# Sheet1.net
KiCad netlist of a schematic drawn in Altium Designer
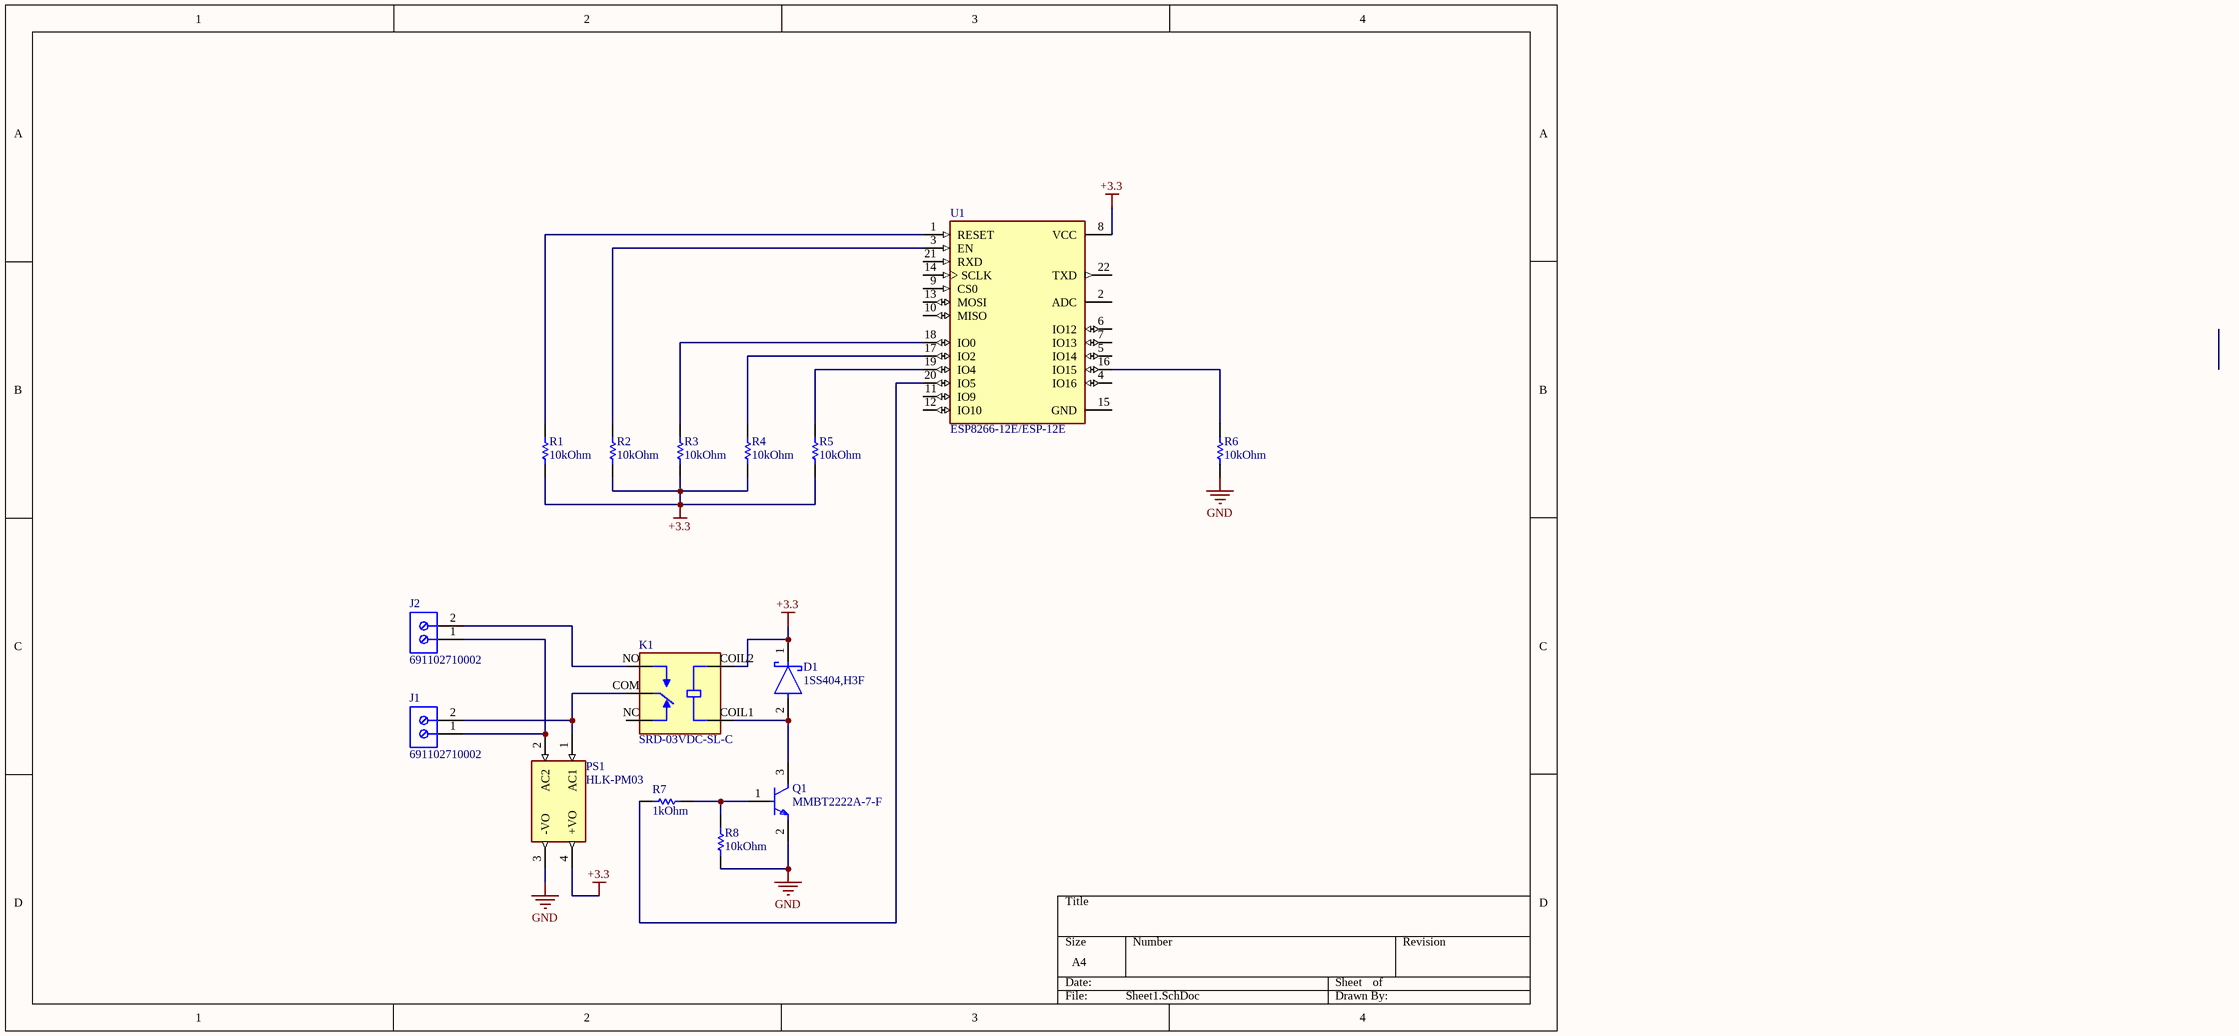
[diagram p0: Sheet1.SchDoc]

(export (version "E")
  (design (tool "Eeschema 10.0.6"))
  (components
    (comp (ref "D1")
      (value "1SS404,H3F")
      (footprint "FP-SOD-323-MFG")
      (description "DIODE SCHOTTKY 20V 300MA USC")
      (libsource (lib "Altium Content Vault") (part "1d6ec82d83fb6aee721767c19dac4b9"))
    )
    (comp (ref "J1")
      (value "691102710002")
      (footprint "691102710002")
      (fields (field (name "VOLTAGE") "300V"))
      (libsource (lib "Altium Content Vault") (part "TBL - 1R - 02P - Screw"))
    )
    (comp (ref "J2")
      (value "691102710002")
      (footprint "691102710002")
      (fields (field (name "VOLTAGE") "300V"))
      (libsource (lib "Altium Content Vault") (part "TBL - 1R - 02P - Screw"))
    )
    (comp (ref "K1")
      (value "SRD-03VDC-SL-C")
      (footprint "SRD-03VDC-SL-C:RELAY_SRD-03VDC-SL-C")
      (fields (field (name "MF") "{'manufacturer': u'Songle Relay'}"))
      (libsource (lib "*") (part "SRD-03VDC-SL-C"))
    )
    (comp (ref "PS1")
      (value "HLK-PM03")
      (footprint "HLK-PM03:CONV_HLK-PM03")
      (fields (field (name "MF") "{'manufacturer': u'Hi-link'}"))
      (libsource (lib "*") (part "HLK-PM03"))
    )
    (comp (ref "Q1")
      (value "MMBT2222A-7-F")
      (footprint "FP-SOT23-IPC_A")
      (description "TRANS NPN 40V 0.6A SMD SOT23-3")
      (fields (field (name "VOLTAGE") "40V"))
      (libsource (lib "Altium Content Vault") (part "b44e953556f554d0102664c7d152cb4"))
    )
    (comp (ref "R1")
      (value "10kOhm")
      (footprint "RESC1609X50X30ML10T20")
      (fields (field (name "MANUFACTURER") "Vishay Dale") (field (name "PART NUMBER") "CRCW060310K0FKTB"))
      (libsource (lib "Altium Content Vault") (part "RES"))
    )
    (comp (ref "R2")
      (value "10kOhm")
      (footprint "RESC1609X50X30ML10T20")
      (fields (field (name "MANUFACTURER") "Vishay Dale") (field (name "PART NUMBER") "CRCW060310K0FKTB"))
      (libsource (lib "Altium Content Vault") (part "RES"))
    )
    (comp (ref "R3")
      (value "10kOhm")
      (footprint "RESC1609X50X30ML10T20")
      (fields (field (name "MANUFACTURER") "Vishay Dale") (field (name "PART NUMBER") "CRCW060310K0FKTB"))
      (libsource (lib "Altium Content Vault") (part "RES"))
    )
    (comp (ref "R4")
      (value "10kOhm")
      (footprint "RESC1609X50X30ML10T20")
      (fields (field (name "MANUFACTURER") "Vishay Dale") (field (name "PART NUMBER") "CRCW060310K0FKTB"))
      (libsource (lib "Altium Content Vault") (part "RES"))
    )
    (comp (ref "R5")
      (value "10kOhm")
      (footprint "RESC1609X50X30ML10T20")
      (fields (field (name "MANUFACTURER") "Vishay Dale") (field (name "PART NUMBER") "CRCW060310K0FKTB"))
      (libsource (lib "Altium Content Vault") (part "RES"))
    )
    (comp (ref "R6")
      (value "10kOhm")
      (footprint "RESC1609X50X30ML10T20")
      (fields (field (name "MANUFACTURER") "Vishay Dale") (field (name "PART NUMBER") "CRCW060310K0FKTB"))
      (libsource (lib "Altium Content Vault") (part "RES"))
    )
    (comp (ref "R7")
      (value "1kOhm")
      (footprint "RESC1609X50X30ML10T20")
      (fields (field (name "MANUFACTURER") "Vishay Dale") (field (name "PART NUMBER") "CRCW060310K0FKTB"))
      (libsource (lib "Altium Content Vault") (part "RES"))
    )
    (comp (ref "R8")
      (value "10kOhm")
      (footprint "RESC1609X50X30ML10T20")
      (fields (field (name "MANUFACTURER") "Vishay Dale") (field (name "PART NUMBER") "CRCW060310K0FKTB"))
      (libsource (lib "Altium Content Vault") (part "RES"))
    )
    (comp (ref "U1")
      (value "ESP8266-12E/ESP-12E")
      (footprint "ESP8266-12E_ESP-12E:XCVR_ESP8266-12E/ESP-12E")
      (description "ESP-12E WiFi Module")
      (fields (field (name "MF") "{'manufacturer': u'AI-Thinker'}"))
      (libsource (lib "*") (part "ESP8266-12E/ESP-12E"))
    )
  )
  (nets
    (net (code "1") (name "+3.3") (class "Default")
      (node (ref "D1") (pin "1") (pinfunction "C_1") (pintype "passive"))
      (node (ref "K1") (pin "COIL2") (pinfunction "COIL2_COIL2") (pintype "passive"))
      (node (ref "PS1") (pin "4") (pinfunction "+VO_4") (pintype "output"))
      (node (ref "R1") (pin "1") (pinfunction "1_1") (pintype "passive"))
      (node (ref "R2") (pin "1") (pinfunction "1_1") (pintype "passive"))
      (node (ref "R3") (pin "1") (pinfunction "1_1") (pintype "passive"))
      (node (ref "R4") (pin "1") (pinfunction "1_1") (pintype "passive"))
      (node (ref "R5") (pin "1") (pinfunction "1_1") (pintype "passive"))
      (node (ref "U1") (pin "8") (pinfunction "VCC_8") (pintype "power_in"))
    )
    (net (code "2") (name "GND") (class "Default")
      (node (ref "PS1") (pin "3") (pinfunction "-VO_3") (pintype "output"))
      (node (ref "Q1") (pin "2") (pinfunction "E_2") (pintype "passive"))
      (node (ref "R6") (pin "1") (pinfunction "1_1") (pintype "passive"))
      (node (ref "R8") (pin "1") (pinfunction "1_1") (pintype "passive"))
    )
    (net (code "3") (name "Net-(D1-A)") (class "Default")
      (node (ref "D1") (pin "2") (pinfunction "A_2") (pintype "passive"))
      (node (ref "K1") (pin "COIL1") (pinfunction "COIL1_COIL1") (pintype "passive"))
      (node (ref "Q1") (pin "3") (pinfunction "C_3") (pintype "passive"))
    )
    (net (code "4") (name "Net-(J2-Pad2)") (class "Default")
      (node (ref "J2") (pin "2") (pinfunction "2_2") (pintype "passive"))
      (node (ref "K1") (pin "NO") (pinfunction "NO_NO") (pintype "passive"))
    )
    (net (code "5") (name "Net-(PS1-AC1)") (class "Default")
      (node (ref "J1") (pin "2") (pinfunction "2_2") (pintype "passive"))
      (node (ref "K1") (pin "COM") (pinfunction "COM_COM") (pintype "passive"))
      (node (ref "PS1") (pin "1") (pinfunction "AC1_1") (pintype "input"))
    )
    (net (code "6") (name "Net-(PS1-AC2)") (class "Default")
      (node (ref "J1") (pin "1") (pinfunction "1_1") (pintype "passive"))
      (node (ref "J2") (pin "1") (pinfunction "1_1") (pintype "passive"))
      (node (ref "PS1") (pin "2") (pinfunction "AC2_2") (pintype "input"))
    )
    (net (code "7") (name "Net-(Q1-B)") (class "Default")
      (node (ref "Q1") (pin "1") (pinfunction "B_1") (pintype "passive"))
      (node (ref "R7") (pin "2") (pinfunction "2_2") (pintype "passive"))
      (node (ref "R8") (pin "2") (pinfunction "2_2") (pintype "passive"))
    )
    (net (code "8") (name "Net-(U1-EN)") (class "Default")
      (node (ref "R2") (pin "2") (pinfunction "2_2") (pintype "passive"))
      (node (ref "U1") (pin "3") (pinfunction "EN_3") (pintype "input"))
    )
    (net (code "9") (name "Net-(U1-IO0)") (class "Default")
      (node (ref "R3") (pin "2") (pinfunction "2_2") (pintype "passive"))
      (node (ref "U1") (pin "18") (pinfunction "IO0_18") (pintype "bidirectional"))
    )
    (net (code "10") (name "Net-(U1-IO2)") (class "Default")
      (node (ref "R4") (pin "2") (pinfunction "2_2") (pintype "passive"))
      (node (ref "U1") (pin "17") (pinfunction "IO2_17") (pintype "bidirectional"))
    )
    (net (code "11") (name "Net-(U1-IO4)") (class "Default")
      (node (ref "R5") (pin "2") (pinfunction "2_2") (pintype "passive"))
      (node (ref "U1") (pin "19") (pinfunction "IO4_19") (pintype "bidirectional"))
    )
    (net (code "12") (name "Net-(U1-IO5)") (class "Default")
      (node (ref "R7") (pin "1") (pinfunction "1_1") (pintype "passive"))
      (node (ref "U1") (pin "20") (pinfunction "IO5_20") (pintype "bidirectional"))
    )
    (net (code "13") (name "Net-(U1-IO15)") (class "Default")
      (node (ref "R6") (pin "2") (pinfunction "2_2") (pintype "passive"))
      (node (ref "U1") (pin "16") (pinfunction "IO15_16") (pintype "bidirectional"))
    )
    (net (code "14") (name "Net-(U1-RESET)") (class "Default")
      (node (ref "R1") (pin "2") (pinfunction "2_2") (pintype "passive"))
      (node (ref "U1") (pin "1") (pinfunction "RESET_1") (pintype "input"))
    )
    (net (code "15") (name "unconnected-(K1-PadNC)") (class "Default")
      (node (ref "K1") (pin "NC") (pinfunction "NC_NC") (pintype "passive"))
    )
    (net (code "16") (name "unconnected-(U1-ADC-Pad2)") (class "Default")
      (node (ref "U1") (pin "2") (pinfunction "ADC_2") (pintype "passive"))
    )
    (net (code "17") (name "unconnected-(U1-CS0-Pad9)") (class "Default")
      (node (ref "U1") (pin "9") (pinfunction "CS0_9") (pintype "input"))
    )
    (net (code "18") (name "unconnected-(U1-GND-Pad15)") (class "Default")
      (node (ref "U1") (pin "15") (pinfunction "GND_15") (pintype "power_in"))
    )
    (net (code "19") (name "unconnected-(U1-IO9-Pad11)") (class "Default")
      (node (ref "U1") (pin "11") (pinfunction "IO9_11") (pintype "bidirectional"))
    )
    (net (code "20") (name "unconnected-(U1-IO10-Pad12)") (class "Default")
      (node (ref "U1") (pin "12") (pinfunction "IO10_12") (pintype "bidirectional"))
    )
    (net (code "21") (name "unconnected-(U1-IO12-Pad6)") (class "Default")
      (node (ref "U1") (pin "6") (pinfunction "IO12_6") (pintype "bidirectional"))
    )
    (net (code "22") (name "unconnected-(U1-IO13-Pad7)") (class "Default")
      (node (ref "U1") (pin "7") (pinfunction "IO13_7") (pintype "bidirectional"))
    )
    (net (code "23") (name "unconnected-(U1-IO14-Pad5)") (class "Default")
      (node (ref "U1") (pin "5") (pinfunction "IO14_5") (pintype "bidirectional"))
    )
    (net (code "24") (name "unconnected-(U1-IO16-Pad4)") (class "Default")
      (node (ref "U1") (pin "4") (pinfunction "IO16_4") (pintype "bidirectional"))
    )
    (net (code "25") (name "unconnected-(U1-MISO-Pad10)") (class "Default")
      (node (ref "U1") (pin "10") (pinfunction "MISO_10") (pintype "bidirectional"))
    )
    (net (code "26") (name "unconnected-(U1-MOSI-Pad13)") (class "Default")
      (node (ref "U1") (pin "13") (pinfunction "MOSI_13") (pintype "bidirectional"))
    )
    (net (code "27") (name "unconnected-(U1-RXD-Pad21)") (class "Default")
      (node (ref "U1") (pin "21") (pinfunction "RXD_21") (pintype "input"))
    )
    (net (code "28") (name "unconnected-(U1-SCLK-Pad14)") (class "Default")
      (node (ref "U1") (pin "14") (pinfunction "SCLK_14") (pintype "input"))
    )
    (net (code "29") (name "unconnected-(U1-TXD-Pad22)") (class "Default")
      (node (ref "U1") (pin "22") (pinfunction "TXD_22") (pintype "output"))
    )
  )
)
